# BuckConverterSchematic.net
KiCad netlist of a schematic drawn in EAGLE
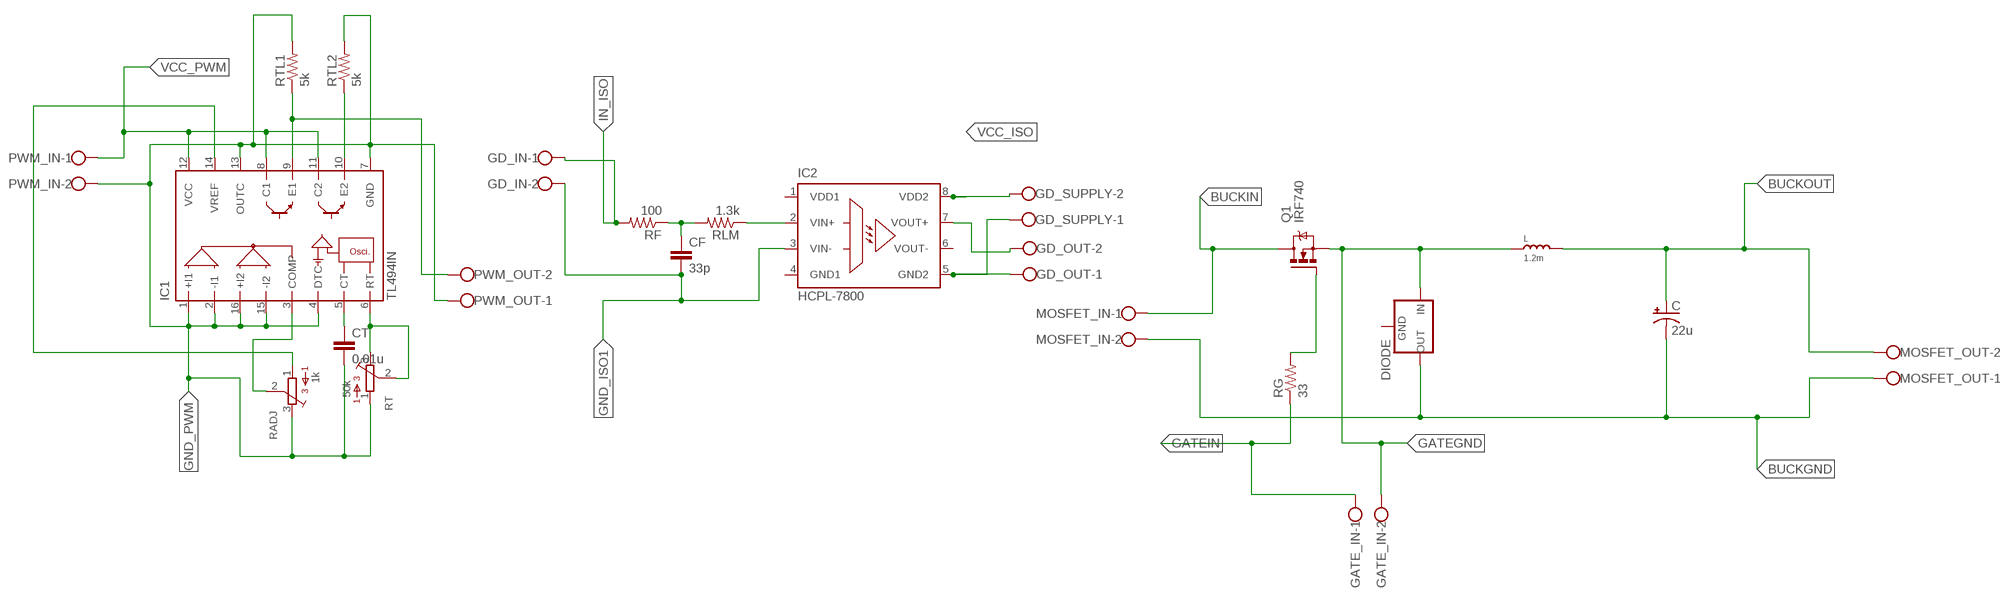
[diagram p0: schematic, sheet 1]

(export (version "E")
  (design (tool "Eeschema 10.0.6"))
  (components
    (comp (ref "C")
      (value "22u")
      (footprint "eagle-import:E2-5")
      (libsource (lib "eagle-import") (part "CPOL-USE2-5"))
    )
    (comp (ref "CF")
      (value "33p")
      (footprint "eagle-import:C025-024X044")
      (libsource (lib "eagle-import") (part "C-EU025-024X044"))
    )
    (comp (ref "CT")
      (value "0.01u")
      (footprint "eagle-import:C025-024X044")
      (libsource (lib "eagle-import") (part "C-EU025-024X044"))
    )
    (comp (ref "DIODE")
      (value "78XXL")
      (footprint "eagle-import:78XXL")
      (libsource (lib "eagle-import") (part "78XXL"))
    )
    (comp (ref "GATE_IN")
      (value "W237-102")
      (footprint "eagle-import:W237-102")
      (fields (field (name "MPN") "237-102"))
      (libsource (lib "eagle-import") (part "W237-102"))
    )
    (comp (ref "GD_IN")
      (value "W237-102")
      (footprint "eagle-import:W237-102")
      (fields (field (name "MPN") "237-102"))
      (libsource (lib "eagle-import") (part "W237-102"))
    )
    (comp (ref "GD_OUT")
      (value "W237-102")
      (footprint "eagle-import:W237-102")
      (fields (field (name "MPN") "237-102"))
      (libsource (lib "eagle-import") (part "W237-102"))
    )
    (comp (ref "GD_SUPPLY")
      (value "W237-102")
      (footprint "eagle-import:W237-102")
      (fields (field (name "MPN") "237-102"))
      (libsource (lib "eagle-import") (part "W237-102"))
    )
    (comp (ref "IC1")
      (value "TL494IN")
      (footprint "eagle-import:DIL16")
      (libsource (lib "eagle-import") (part "TL494NI"))
    )
    (comp (ref "IC2")
      (value "HCPL-7800")
      (footprint "eagle-import:DIL08")
      (fields (field (name "MPN") "HCPL-7800A#500"))
      (libsource (lib "eagle-import") (part "HCPL-7800"))
    )
    (comp (ref "L")
      (value "1.2m")
      (footprint "eagle-import:FERRITE-CORE-INDUCTOR")
      (libsource (lib "eagle-import") (part "HIGH-FREQUENCY-POWER-INDUCTOR"))
    )
    (comp (ref "MOSFET_IN")
      (value "W237-102")
      (footprint "eagle-import:W237-102")
      (fields (field (name "MPN") "237-102"))
      (libsource (lib "eagle-import") (part "W237-102"))
    )
    (comp (ref "MOSFET_OUT")
      (value "W237-102")
      (footprint "eagle-import:W237-102")
      (fields (field (name "MPN") "237-102"))
      (libsource (lib "eagle-import") (part "W237-102"))
    )
    (comp (ref "PWM_IN")
      (value "W237-102")
      (footprint "eagle-import:W237-102")
      (fields (field (name "MPN") "237-102"))
      (libsource (lib "eagle-import") (part "W237-102"))
    )
    (comp (ref "PWM_OUT")
      (value "W237-102")
      (footprint "eagle-import:W237-102")
      (fields (field (name "MPN") "237-102"))
      (libsource (lib "eagle-import") (part "W237-102"))
    )
    (comp (ref "Q1")
      (value "IRF740")
      (footprint "eagle-import:TO220BV")
      (libsource (lib "eagle-import") (part "IRF740"))
    )
    (comp (ref "RADJ")
      (value "1k")
      (footprint "eagle-import:3386P")
      (libsource (lib "eagle-import") (part "3386-P"))
    )
    (comp (ref "RF")
      (value "100")
      (footprint "eagle-import:0207_9")
      (libsource (lib "eagle-import") (part "R-US_0207/9"))
    )
    (comp (ref "RG")
      (value "33")
      (footprint "eagle-import:0411_15")
      (libsource (lib "eagle-import") (part "R-US_0411/15"))
    )
    (comp (ref "RLM")
      (value "1.3k")
      (footprint "eagle-import:0207_9")
      (libsource (lib "eagle-import") (part "R-US_0207/9"))
    )
    (comp (ref "RT")
      (value "50k")
      (footprint "eagle-import:3386P")
      (libsource (lib "eagle-import") (part "3386-P"))
    )
    (comp (ref "RTL1")
      (value "5k")
      (footprint "eagle-import:0207_9")
      (libsource (lib "eagle-import") (part "R-US_0207/9"))
    )
    (comp (ref "RTL2")
      (value "5k")
      (footprint "eagle-import:0207_9")
      (libsource (lib "eagle-import") (part "R-US_0207/9"))
    )
  )
  (nets
    (net (code "1") (name "/GND1") (class "Default")
      (node (ref "IC2") (pin "4") (pinfunction "GND1_4") (pintype "power_in"))
    )
    (net (code "2") (name "/VDD1") (class "Default")
      (node (ref "IC2") (pin "1") (pinfunction "VDD1_1") (pintype "power_in"))
    )
    (net (code "3") (name "/VOUT-") (class "Default")
      (node (ref "IC2") (pin "6") (pinfunction "VOUT-_6") (pintype "power_in"))
    )
    (net (code "4") (name "BUCKGND") (class "Default")
      (node (ref "C") (pin "-") (pinfunction "-_-") (pintype "passive"))
      (node (ref "DIODE") (pin "OUT") (pinfunction "OUT_OUT") (pintype "passive"))
      (node (ref "MOSFET_IN") (pin "2") (pinfunction "KL_2") (pintype "passive"))
      (node (ref "MOSFET_OUT") (pin "1") (pinfunction "KL_1") (pintype "passive"))
    )
    (net (code "5") (name "BUCKIN") (class "Default")
      (node (ref "MOSFET_IN") (pin "1") (pinfunction "KL_1") (pintype "passive"))
      (node (ref "Q1") (pin "D") (pinfunction "D_D") (pintype "passive"))
    )
    (net (code "6") (name "BUCKOUT") (class "Default")
      (node (ref "C") (pin "+") (pinfunction "+_+") (pintype "passive"))
      (node (ref "L") (pin "P$2") (pinfunction "L2_P$2") (pintype "passive"))
      (node (ref "MOSFET_OUT") (pin "2") (pinfunction "KL_2") (pintype "passive"))
    )
    (net (code "7") (name "GATEGND") (class "Default")
      (node (ref "DIODE") (pin "IN") (pinfunction "IN_IN") (pintype "input"))
      (node (ref "GATE_IN") (pin "2") (pinfunction "KL_2") (pintype "passive"))
      (node (ref "L") (pin "P$1") (pinfunction "L1_P$1") (pintype "passive"))
      (node (ref "Q1") (pin "S") (pinfunction "S_S") (pintype "passive"))
    )
    (net (code "8") (name "GATEIN") (class "Default")
      (node (ref "GATE_IN") (pin "1") (pinfunction "KL_1") (pintype "passive"))
      (node (ref "RG") (pin "1") (pinfunction "1_1") (pintype "passive"))
    )
    (net (code "9") (name "GND_ISO1") (class "Default")
      (node (ref "CF") (pin "2") (pinfunction "2_2") (pintype "passive"))
      (node (ref "GD_IN") (pin "2") (pinfunction "KL_2") (pintype "passive"))
      (node (ref "IC2") (pin "3") (pinfunction "VIN-_3") (pintype "power_in"))
    )
    (net (code "10") (name "GND_PWM") (class "Default")
      (node (ref "CT") (pin "2") (pinfunction "2_2") (pintype "passive"))
      (node (ref "IC1") (pin "1") (pinfunction "+I1_1") (pintype "input"))
      (node (ref "IC1") (pin "13") (pinfunction "OUTC_13") (pintype "output"))
      (node (ref "IC1") (pin "15") (pinfunction "-I2_15") (pintype "input"))
      (node (ref "IC1") (pin "16") (pinfunction "+I2_16") (pintype "input"))
      (node (ref "IC1") (pin "2") (pinfunction "-I1_2") (pintype "input"))
      (node (ref "IC1") (pin "4") (pinfunction "DTC_4") (pintype "input"))
      (node (ref "IC1") (pin "7") (pinfunction "GND_7") (pintype "power_in"))
      (node (ref "PWM_IN") (pin "2") (pinfunction "KL_2") (pintype "passive"))
      (node (ref "PWM_OUT") (pin "1") (pinfunction "KL_1") (pintype "passive"))
      (node (ref "RADJ") (pin "3") (pinfunction "3_3") (pintype "passive"))
      (node (ref "RT") (pin "1") (pinfunction "1_1") (pintype "passive"))
      (node (ref "RTL1") (pin "2") (pinfunction "2_2") (pintype "passive"))
      (node (ref "RTL2") (pin "2") (pinfunction "2_2") (pintype "passive"))
    )
    (net (code "11") (name "IN_ISO") (class "Default")
      (node (ref "GD_IN") (pin "1") (pinfunction "KL_1") (pintype "passive"))
      (node (ref "RF") (pin "2") (pinfunction "2_2") (pintype "passive"))
    )
    (net (code "12") (name "Net-(CF-Pad1)") (class "Default")
      (node (ref "CF") (pin "1") (pinfunction "1_1") (pintype "passive"))
      (node (ref "RF") (pin "1") (pinfunction "1_1") (pintype "passive"))
      (node (ref "RLM") (pin "2") (pinfunction "2_2") (pintype "passive"))
    )
    (net (code "13") (name "Net-(GD_OUTA-KL)") (class "Default")
      (node (ref "GD_OUT") (pin "1") (pinfunction "KL_1") (pintype "passive"))
      (node (ref "GD_SUPPLY") (pin "1") (pinfunction "KL_1") (pintype "passive"))
      (node (ref "IC2") (pin "5") (pinfunction "GND2_5") (pintype "power_in"))
    )
    (net (code "14") (name "Net-(GD_OUTB-KL)") (class "Default")
      (node (ref "GD_OUT") (pin "2") (pinfunction "KL_2") (pintype "passive"))
      (node (ref "IC2") (pin "7") (pinfunction "VOUT+_7") (pintype "power_in"))
    )
    (net (code "15") (name "Net-(IC1-COMP)") (class "Default")
      (node (ref "IC1") (pin "3") (pinfunction "COMP_3") (pintype "passive"))
      (node (ref "RADJ") (pin "2") (pinfunction "2_2") (pintype "passive"))
    )
    (net (code "16") (name "Net-(IC1-CT)") (class "Default")
      (node (ref "CT") (pin "1") (pinfunction "1_1") (pintype "passive"))
      (node (ref "IC1") (pin "5") (pinfunction "CT_5") (pintype "input"))
    )
    (net (code "17") (name "Net-(IC1-E1)") (class "Default")
      (node (ref "IC1") (pin "9") (pinfunction "E1_9") (pintype "passive"))
      (node (ref "PWM_OUT") (pin "2") (pinfunction "KL_2") (pintype "passive"))
      (node (ref "RTL1") (pin "1") (pinfunction "1_1") (pintype "passive"))
    )
    (net (code "18") (name "Net-(IC1-E2)") (class "Default")
      (node (ref "IC1") (pin "10") (pinfunction "E2_10") (pintype "passive"))
      (node (ref "RTL2") (pin "1") (pinfunction "1_1") (pintype "passive"))
    )
    (net (code "19") (name "Net-(IC1-RT)") (class "Default")
      (node (ref "IC1") (pin "6") (pinfunction "RT_6") (pintype "input"))
      (node (ref "RT") (pin "2") (pinfunction "2_2") (pintype "passive"))
      (node (ref "RT") (pin "3") (pinfunction "3_3") (pintype "passive"))
    )
    (net (code "20") (name "Net-(IC1-VREF)") (class "Default")
      (node (ref "IC1") (pin "14") (pinfunction "VREF_14") (pintype "input"))
      (node (ref "RADJ") (pin "1") (pinfunction "1_1") (pintype "passive"))
    )
    (net (code "21") (name "Net-(IC2-VIN+)") (class "Default")
      (node (ref "IC2") (pin "2") (pinfunction "VIN+_2") (pintype "power_in"))
      (node (ref "RLM") (pin "1") (pinfunction "1_1") (pintype "passive"))
    )
    (net (code "22") (name "Net-(Q1-PadG)") (class "Default")
      (node (ref "Q1") (pin "G") (pinfunction "G_G") (pintype "passive"))
      (node (ref "RG") (pin "2") (pinfunction "2_2") (pintype "passive"))
    )
    (net (code "23") (name "VCC_ISO") (class "Default")
      (node (ref "GD_SUPPLY") (pin "2") (pinfunction "KL_2") (pintype "passive"))
      (node (ref "IC2") (pin "8") (pinfunction "VDD2_8") (pintype "power_in"))
    )
    (net (code "24") (name "VCC_PWM") (class "Default")
      (node (ref "IC1") (pin "11") (pinfunction "C2_11") (pintype "passive"))
      (node (ref "IC1") (pin "12") (pinfunction "VCC_12") (pintype "power_in"))
      (node (ref "IC1") (pin "8") (pinfunction "C1_8") (pintype "passive"))
      (node (ref "PWM_IN") (pin "1") (pinfunction "KL_1") (pintype "passive"))
    )
    (net (code "25") (name "unconnected-(DIODE-PadGND)") (class "Default")
      (node (ref "DIODE") (pin "GND") (pinfunction "GND_GND") (pintype "input"))
    )
  )
)
